# 03_-_CPU_POWER.net
KiCad netlist of a schematic drawn in Altium Designer
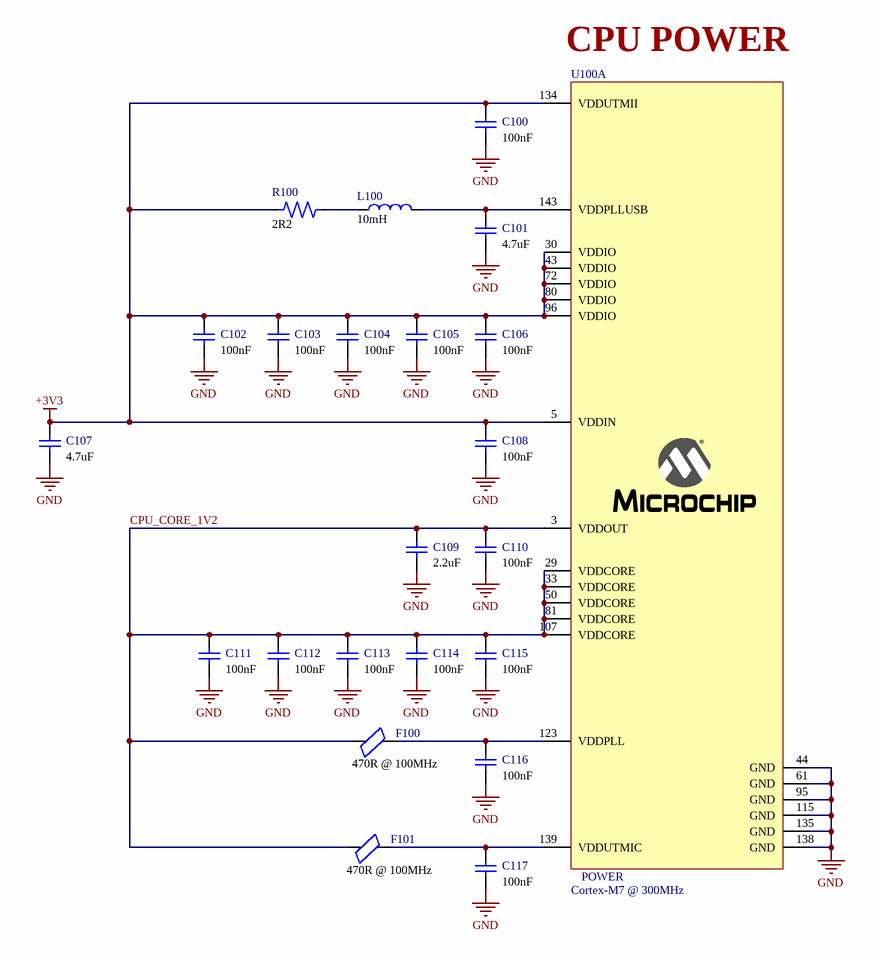
[diagram p0: [03] - CPU POWER.SchDoc]

(export (version "E")
  (design (tool "Eeschema 10.0.6"))
  (components
    (comp (ref "C100")
      (value "100nF")
      (footprint "C0402")
      (description "C0402")
      (fields (field (name "Comment") "04023C103KAT2A"))
      (libsource (lib "Passive components") (part "04023C103KAT2A"))
    )
    (comp (ref "C101")
      (value "4.7uF")
      (footprint "C0603")
      (description "C0603")
      (fields (field (name "Comment") "02016D104KAT2A"))
      (libsource (lib "Passive components") (part "02016D104KAT2A"))
    )
    (comp (ref "C102")
      (value "100nF")
      (footprint "C0402")
      (description "C0402")
      (fields (field (name "Comment") "04023C103KAT2A"))
      (libsource (lib "Passive components") (part "04023C103KAT2A"))
    )
    (comp (ref "C103")
      (value "100nF")
      (footprint "C0402")
      (description "C0402")
      (fields (field (name "Comment") "04023C103KAT2A"))
      (libsource (lib "Passive components") (part "04023C103KAT2A"))
    )
    (comp (ref "C104")
      (value "100nF")
      (footprint "C0402")
      (description "C0402")
      (fields (field (name "Comment") "04023C103KAT2A"))
      (libsource (lib "Passive components") (part "04023C103KAT2A"))
    )
    (comp (ref "C105")
      (value "100nF")
      (footprint "C0402")
      (description "C0402")
      (fields (field (name "Comment") "04023C103KAT2A"))
      (libsource (lib "Passive components") (part "04023C103KAT2A"))
    )
    (comp (ref "C106")
      (value "100nF")
      (footprint "C0402")
      (description "C0402")
      (fields (field (name "Comment") "04023C103KAT2A"))
      (libsource (lib "Passive components") (part "04023C103KAT2A"))
    )
    (comp (ref "C107")
      (value "4.7uF")
      (footprint "C0603")
      (description "C0603")
      (fields (field (name "Comment") "02016D104KAT2A"))
      (libsource (lib "Passive components") (part "02016D104KAT2A"))
    )
    (comp (ref "C108")
      (value "100nF")
      (footprint "C0402")
      (description "C0402")
      (fields (field (name "Comment") "04023C103KAT2A"))
      (libsource (lib "Passive components") (part "04023C103KAT2A"))
    )
    (comp (ref "C109")
      (value "2.2uF")
      (footprint "C0402")
      (description "C0402")
      (fields (field (name "Comment") "04023C103KAT2A"))
      (libsource (lib "Passive components") (part "04023C103KAT2A"))
    )
    (comp (ref "C110")
      (value "100nF")
      (footprint "C0402")
      (description "C0402")
      (fields (field (name "Comment") "04023C103KAT2A"))
      (libsource (lib "Passive components") (part "04023C103KAT2A"))
    )
    (comp (ref "C111")
      (value "100nF")
      (footprint "C0402")
      (description "C0402")
      (fields (field (name "Comment") "04023C103KAT2A"))
      (libsource (lib "Passive components") (part "04023C103KAT2A"))
    )
    (comp (ref "C112")
      (value "100nF")
      (footprint "C0402")
      (description "C0402")
      (fields (field (name "Comment") "04023C103KAT2A"))
      (libsource (lib "Passive components") (part "04023C103KAT2A"))
    )
    (comp (ref "C113")
      (value "100nF")
      (footprint "C0402")
      (description "C0402")
      (fields (field (name "Comment") "04023C103KAT2A"))
      (libsource (lib "Passive components") (part "04023C103KAT2A"))
    )
    (comp (ref "C114")
      (value "100nF")
      (footprint "C0402")
      (description "C0402")
      (fields (field (name "Comment") "04023C103KAT2A"))
      (libsource (lib "Passive components") (part "04023C103KAT2A"))
    )
    (comp (ref "C115")
      (value "100nF")
      (footprint "C0402")
      (description "C0402")
      (fields (field (name "Comment") "04023C103KAT2A"))
      (libsource (lib "Passive components") (part "04023C103KAT2A"))
    )
    (comp (ref "C116")
      (value "100nF")
      (footprint "C0402")
      (description "C0402")
      (fields (field (name "Comment") "04023C103KAT2A"))
      (libsource (lib "Passive components") (part "04023C103KAT2A"))
    )
    (comp (ref "C117")
      (value "100nF")
      (footprint "C0402")
      (description "C0402")
      (fields (field (name "Comment") "04023C103KAT2A"))
      (libsource (lib "Passive components") (part "04023C103KAT2A"))
    )
    (comp (ref "F100")
      (value "470R @ 100MHz")
      (footprint "Ferrite bead 0402")
      (description "Ferrite bead 0402")
      (fields (field (name "Comment") "BLM15AG102SN1D"))
      (libsource (lib "Passive components") (part "BLM15AG102SN1D"))
    )
    (comp (ref "F101")
      (value "470R @ 100MHz")
      (footprint "Ferrite bead 0402")
      (description "Ferrite bead 0402")
      (fields (field (name "Comment") "BLM15AG102SN1D"))
      (libsource (lib "Passive components") (part "BLM15AG102SN1D"))
    )
    (comp (ref "L100")
      (value "10mH")
      (footprint "Inductor 0603")
      (description "Inductor 0603")
      (fields (field (name "Comment") "MLZ1608A2R2WT"))
      (libsource (lib "Passive components") (part "MLZ1608A2R2WT"))
    )
    (comp (ref "R100")
      (value "2R2")
      (footprint "R0402")
      (description "R0402")
      (fields (field (name "Comment") "CRCW04020000Z0ED"))
      (libsource (lib "Passive components") (part "CRCW04020000Z0ED"))
    )
    (comp (ref "U100")
      (value "Cortex-M7 @ 300MHz")
      (footprint "ATSAMS70Q21A-AN")
      (description "ATSAMS70Q21")
      (libsource (lib "Microcontrollers") (part "ATSAMS70Q21A-AN"))
    )
  )
  (nets
    (net (code "1") (name "+3V3") (class "Default")
      (node (ref "C100") (pin "2") (pinfunction "2_2") (pintype "passive"))
      (node (ref "C102") (pin "2") (pinfunction "2_2") (pintype "passive"))
      (node (ref "C103") (pin "2") (pinfunction "2_2") (pintype "passive"))
      (node (ref "C104") (pin "2") (pinfunction "2_2") (pintype "passive"))
      (node (ref "C105") (pin "2") (pinfunction "2_2") (pintype "passive"))
      (node (ref "C106") (pin "2") (pinfunction "2_2") (pintype "passive"))
      (node (ref "C107") (pin "2") (pinfunction "2_2") (pintype "passive"))
      (node (ref "C108") (pin "2") (pinfunction "2_2") (pintype "passive"))
      (node (ref "R100") (pin "1") (pinfunction "1_1") (pintype "passive"))
      (node (ref "U100") (pin "134") (pinfunction "VDDUTMII_134") (pintype "power_in"))
      (node (ref "U100") (pin "30") (pinfunction "VDDIO_30") (pintype "power_in"))
      (node (ref "U100") (pin "43") (pinfunction "VDDIO_43") (pintype "power_in"))
      (node (ref "U100") (pin "5") (pinfunction "VDDIN_5") (pintype "power_in"))
      (node (ref "U100") (pin "72") (pinfunction "VDDIO_72") (pintype "power_in"))
      (node (ref "U100") (pin "80") (pinfunction "VDDIO_80") (pintype "power_in"))
      (node (ref "U100") (pin "96") (pinfunction "VDDIO_96") (pintype "power_in"))
    )
    (net (code "2") (name "/CPU_CORE_1V2") (class "Default")
      (node (ref "C109") (pin "2") (pinfunction "2_2") (pintype "passive"))
      (node (ref "C110") (pin "2") (pinfunction "2_2") (pintype "passive"))
      (node (ref "C111") (pin "2") (pinfunction "2_2") (pintype "passive"))
      (node (ref "C112") (pin "2") (pinfunction "2_2") (pintype "passive"))
      (node (ref "C113") (pin "2") (pinfunction "2_2") (pintype "passive"))
      (node (ref "C114") (pin "2") (pinfunction "2_2") (pintype "passive"))
      (node (ref "C115") (pin "2") (pinfunction "2_2") (pintype "passive"))
      (node (ref "F100") (pin "1") (pinfunction "1_1") (pintype "passive"))
      (node (ref "F101") (pin "1") (pinfunction "1_1") (pintype "passive"))
      (node (ref "U100") (pin "107") (pinfunction "VDDCORE_107") (pintype "power_in"))
      (node (ref "U100") (pin "29") (pinfunction "VDDCORE_29") (pintype "power_in"))
      (node (ref "U100") (pin "3") (pinfunction "VDDOUT_3") (pintype "power_in"))
      (node (ref "U100") (pin "33") (pinfunction "VDDCORE_33") (pintype "power_in"))
      (node (ref "U100") (pin "50") (pinfunction "VDDCORE_50") (pintype "power_in"))
      (node (ref "U100") (pin "81") (pinfunction "VDDCORE_81") (pintype "power_in"))
    )
    (net (code "3") (name "GND") (class "Default")
      (node (ref "C100") (pin "1") (pinfunction "1_1") (pintype "passive"))
      (node (ref "C101") (pin "1") (pinfunction "1_1") (pintype "passive"))
      (node (ref "C102") (pin "1") (pinfunction "1_1") (pintype "passive"))
      (node (ref "C103") (pin "1") (pinfunction "1_1") (pintype "passive"))
      (node (ref "C104") (pin "1") (pinfunction "1_1") (pintype "passive"))
      (node (ref "C105") (pin "1") (pinfunction "1_1") (pintype "passive"))
      (node (ref "C106") (pin "1") (pinfunction "1_1") (pintype "passive"))
      (node (ref "C107") (pin "1") (pinfunction "1_1") (pintype "passive"))
      (node (ref "C108") (pin "1") (pinfunction "1_1") (pintype "passive"))
      (node (ref "C109") (pin "1") (pinfunction "1_1") (pintype "passive"))
      (node (ref "C110") (pin "1") (pinfunction "1_1") (pintype "passive"))
      (node (ref "C111") (pin "1") (pinfunction "1_1") (pintype "passive"))
      (node (ref "C112") (pin "1") (pinfunction "1_1") (pintype "passive"))
      (node (ref "C113") (pin "1") (pinfunction "1_1") (pintype "passive"))
      (node (ref "C114") (pin "1") (pinfunction "1_1") (pintype "passive"))
      (node (ref "C115") (pin "1") (pinfunction "1_1") (pintype "passive"))
      (node (ref "C116") (pin "1") (pinfunction "1_1") (pintype "passive"))
      (node (ref "C117") (pin "1") (pinfunction "1_1") (pintype "passive"))
      (node (ref "U100") (pin "115") (pinfunction "GND_115") (pintype "power_in"))
      (node (ref "U100") (pin "135") (pinfunction "GND_135") (pintype "power_in"))
      (node (ref "U100") (pin "138") (pinfunction "GND_138") (pintype "power_in"))
      (node (ref "U100") (pin "44") (pinfunction "GND_44") (pintype "power_in"))
      (node (ref "U100") (pin "61") (pinfunction "GND_61") (pintype "power_in"))
      (node (ref "U100") (pin "95") (pinfunction "GND_95") (pintype "power_in"))
    )
    (net (code "4") (name "Net-(R100-3)") (class "Default")
      (node (ref "L100") (pin "1") (pinfunction "1_1") (pintype "passive"))
      (node (ref "R100") (pin "2") (pinfunction "3_2") (pintype "passive"))
    )
    (net (code "5") (name "Net-(U100A-VDDPLL)") (class "Default")
      (node (ref "C116") (pin "2") (pinfunction "2_2") (pintype "passive"))
      (node (ref "F100") (pin "2") (pinfunction "2_2") (pintype "passive"))
      (node (ref "U100") (pin "123") (pinfunction "VDDPLL_123") (pintype "power_in"))
    )
    (net (code "6") (name "Net-(U100A-VDDPLLUSB)") (class "Default")
      (node (ref "C101") (pin "2") (pinfunction "2_2") (pintype "passive"))
      (node (ref "L100") (pin "2") (pinfunction "2_2") (pintype "passive"))
      (node (ref "U100") (pin "143") (pinfunction "VDDPLLUSB_143") (pintype "power_in"))
    )
    (net (code "7") (name "Net-(U100A-VDDUTMIC)") (class "Default")
      (node (ref "C117") (pin "2") (pinfunction "2_2") (pintype "passive"))
      (node (ref "F101") (pin "2") (pinfunction "2_2") (pintype "passive"))
      (node (ref "U100") (pin "139") (pinfunction "VDDUTMIC_139") (pintype "power_in"))
    )
  )
)
